# 5V0_12V0_rails.net
KiCad netlist of a schematic drawn in Altium Designer
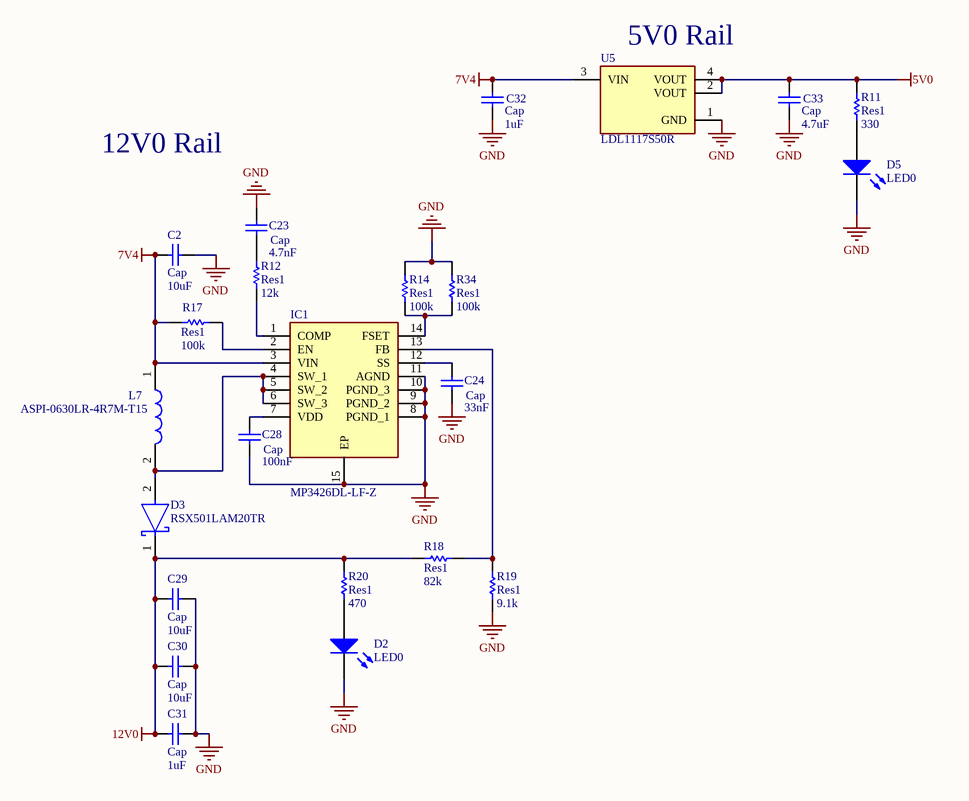
[diagram p0: 5V0 +12V0 rails.SchDoc]

(export (version "E")
  (design (tool "Eeschema 10.0.6"))
  (components
    (comp (ref "C2")
      (value "Cap")
      (footprint "6-0805_M")
      (description "Capacitor")
      (fields (field (name "ALTIUM_VALUE") "10uF") (field (name "PUBLISHER") "Altium Limited"))
      (libsource (lib "Miscellaneous Devices") (part "Cap"))
    )
    (comp (ref "C23")
      (value "Cap")
      (footprint "0402-A")
      (description "Capacitor")
      (fields (field (name "ALTIUM_VALUE") "4.7nF") (field (name "PUBLISHER") "Altium Limited"))
      (libsource (lib "Miscellaneous Devices") (part "Cap"))
    )
    (comp (ref "C24")
      (value "Cap")
      (footprint "0402-A")
      (description "Capacitor")
      (fields (field (name "ALTIUM_VALUE") "33nF") (field (name "PUBLISHER") "Altium Limited"))
      (libsource (lib "Miscellaneous Devices") (part "Cap"))
    )
    (comp (ref "C28")
      (value "Cap")
      (footprint "1608[0603]")
      (description "Capacitor")
      (fields (field (name "ALTIUM_VALUE") "100nF") (field (name "PUBLISHER") "Altium Limited"))
      (libsource (lib "Miscellaneous Devices") (part "Cap"))
    )
    (comp (ref "C29")
      (value "Cap")
      (footprint "6-0805_M")
      (description "Capacitor")
      (fields (field (name "ALTIUM_VALUE") "10uF") (field (name "PUBLISHER") "Altium Limited"))
      (libsource (lib "Miscellaneous Devices") (part "Cap"))
    )
    (comp (ref "C30")
      (value "Cap")
      (footprint "6-0805_M")
      (description "Capacitor")
      (fields (field (name "ALTIUM_VALUE") "10uF") (field (name "PUBLISHER") "Altium Limited"))
      (libsource (lib "Miscellaneous Devices") (part "Cap"))
    )
    (comp (ref "C31")
      (value "Cap")
      (footprint "1608[0603]")
      (description "Capacitor")
      (fields (field (name "ALTIUM_VALUE") "1uF") (field (name "PUBLISHER") "Altium Limited"))
      (libsource (lib "Miscellaneous Devices") (part "Cap"))
    )
    (comp (ref "C32")
      (value "Cap")
      (footprint "1608[0603]")
      (description "Capacitor")
      (fields (field (name "ALTIUM_VALUE") "1uF") (field (name "PUBLISHER") "Altium Limited"))
      (libsource (lib "Miscellaneous Devices") (part "Cap"))
    )
    (comp (ref "C33")
      (value "Cap")
      (footprint "1608[0603]")
      (description "Capacitor")
      (fields (field (name "ALTIUM_VALUE") "4.7uF") (field (name "PUBLISHER") "Altium Limited"))
      (libsource (lib "Miscellaneous Devices") (part "Cap"))
    )
    (comp (ref "D2")
      (value "LED0")
      (footprint "1608[0603]")
      (fields (field (name "PUBLISHER") "Altium Limited"))
      (libsource (lib "Miscellaneous Devices") (part "LED0"))
    )
    (comp (ref "D3")
      (value "RSX501LAM20TR")
      (footprint "FP-PMDTM-MFG")
      (description "DIODE SCHOTTKY 20V 5A PMDTM")
      (fields
        (field (name "OCTOPART") "https://octopart.com/rsx501lam20tr-rohm-82270774")
        (field (name "MANUFACTURER") "Rohm")
      )
      (libsource (lib "Altium Content Vault") (part "1d6ec82d83fb6aee721767c19dac4b9"))
    )
    (comp (ref "D5")
      (value "LED0")
      (footprint "1608[0603]")
      (fields (field (name "PUBLISHER") "Altium Limited"))
      (libsource (lib "Miscellaneous Devices") (part "LED0"))
    )
    (comp (ref "IC1")
      (value "MP3426DL-LF-Z")
      (footprint "SamacSys:SON50P300X400X100-15N-D")
      (description "Integrated Circuit")
      (fields (field (name "MOUSER PART NUMBER") "946-MP3426DL-LF-Z"))
      (libsource (lib "*") (part "MP3426DL-LF-Z"))
    )
    (comp (ref "L7")
      (value "ASPI-0630LR-4R7M-T15")
      (footprint "SamacSys:ASPI-0630LR")
      (description "Inductor")
      (fields (field (name "MOUSER PART NUMBER") "815-ASPI0630LR4R7T15"))
      (libsource (lib "*") (part "ASPI-0630LR-4R7M-T15"))
    )
    (comp (ref "R11")
      (value "Res1")
      (footprint "0402-A")
      (description "Resistor")
      (fields (field (name "ALTIUM_VALUE") "330") (field (name "PUBLISHER") "Altium Limited"))
      (libsource (lib "Miscellaneous Devices") (part "Res1"))
    )
    (comp (ref "R12")
      (value "Res1")
      (footprint "0402-A")
      (description "Resistor")
      (fields (field (name "ALTIUM_VALUE") "12k") (field (name "PUBLISHER") "Altium Limited"))
      (libsource (lib "Miscellaneous Devices") (part "Res1"))
    )
    (comp (ref "R14")
      (value "Res1")
      (footprint "0402-A")
      (description "Resistor")
      (fields (field (name "ALTIUM_VALUE") "100k") (field (name "PUBLISHER") "Altium Limited"))
      (libsource (lib "Miscellaneous Devices") (part "Res1"))
    )
    (comp (ref "R17")
      (value "Res1")
      (footprint "0402-A")
      (description "Resistor")
      (fields (field (name "ALTIUM_VALUE") "100k") (field (name "PUBLISHER") "Altium Limited"))
      (libsource (lib "Miscellaneous Devices") (part "Res1"))
    )
    (comp (ref "R18")
      (value "Res1")
      (footprint "0402-A")
      (description "Resistor")
      (fields (field (name "ALTIUM_VALUE") "82k") (field (name "PUBLISHER") "Altium Limited"))
      (libsource (lib "Miscellaneous Devices") (part "Res1"))
    )
    (comp (ref "R19")
      (value "Res1")
      (footprint "0402-A")
      (description "Resistor")
      (fields (field (name "ALTIUM_VALUE") "9.1k") (field (name "PUBLISHER") "Altium Limited"))
      (libsource (lib "Miscellaneous Devices") (part "Res1"))
    )
    (comp (ref "R20")
      (value "Res1")
      (footprint "6-0805_M")
      (description "Resistor")
      (fields (field (name "ALTIUM_VALUE") "470") (field (name "PUBLISHER") "Altium Limited"))
      (libsource (lib "Miscellaneous Devices") (part "Res1"))
    )
    (comp (ref "R34")
      (value "Res1")
      (footprint "0402-A")
      (description "Resistor")
      (fields (field (name "ALTIUM_VALUE") "100k") (field (name "PUBLISHER") "Altium Limited"))
      (libsource (lib "Miscellaneous Devices") (part "Res1"))
    )
    (comp (ref "U5")
      (value "LDL1117S50R")
      (footprint "FP-SOT-223-0046067_14-MFG")
      (description "IC REG LINEAR 5V 1.2A SOT223")
      (fields
        (field (name "OCTOPART") "https://octopart.com/ldl1117s50r-stmicroelectronics-81876164")
        (field (name "MANUFACTURER") "STMicroelectronics")
      )
      (libsource (lib "Altium Content Vault") (part "a368f1d72361ca9956852d636243424"))
    )
  )
  (nets
    (net (code "1") (name "5V0") (class "Default")
      (node (ref "C33") (pin "2") (pinfunction "2_2") (pintype "passive"))
      (node (ref "R11") (pin "2") (pinfunction "2_2") (pintype "passive"))
      (node (ref "U5") (pin "2") (pinfunction "VOUT_2") (pintype "power_in"))
      (node (ref "U5") (pin "4") (pinfunction "VOUT_4") (pintype "power_in"))
    )
    (net (code "2") (name "7V4") (class "Default")
      (node (ref "C2") (pin "2") (pinfunction "2_2") (pintype "passive"))
      (node (ref "C32") (pin "2") (pinfunction "2_2") (pintype "passive"))
      (node (ref "IC1") (pin "3") (pinfunction "VIN_3") (pintype "passive"))
      (node (ref "L7") (pin "1") (pinfunction "1_1") (pintype "passive"))
      (node (ref "R17") (pin "2") (pinfunction "2_2") (pintype "passive"))
      (node (ref "U5") (pin "3") (pinfunction "VIN_3") (pintype "power_in"))
    )
    (net (code "3") (name "12V0") (class "Default")
      (node (ref "C29") (pin "2") (pinfunction "2_2") (pintype "passive"))
      (node (ref "C30") (pin "2") (pinfunction "2_2") (pintype "passive"))
      (node (ref "C31") (pin "2") (pinfunction "2_2") (pintype "passive"))
      (node (ref "D3") (pin "1") (pinfunction "C_1") (pintype "passive"))
      (node (ref "R18") (pin "2") (pinfunction "2_2") (pintype "passive"))
      (node (ref "R20") (pin "2") (pinfunction "2_2") (pintype "passive"))
    )
    (net (code "4") (name "GND") (class "Default")
      (node (ref "C2") (pin "1") (pinfunction "1_1") (pintype "passive"))
      (node (ref "C23") (pin "2") (pinfunction "2_2") (pintype "passive"))
      (node (ref "C24") (pin "1") (pinfunction "1_1") (pintype "passive"))
      (node (ref "C28") (pin "1") (pinfunction "1_1") (pintype "passive"))
      (node (ref "C29") (pin "1") (pinfunction "1_1") (pintype "passive"))
      (node (ref "C30") (pin "1") (pinfunction "1_1") (pintype "passive"))
      (node (ref "C31") (pin "1") (pinfunction "1_1") (pintype "passive"))
      (node (ref "C32") (pin "1") (pinfunction "1_1") (pintype "passive"))
      (node (ref "C33") (pin "1") (pinfunction "1_1") (pintype "passive"))
      (node (ref "D2") (pin "2") (pinfunction "K_2") (pintype "passive"))
      (node (ref "D5") (pin "2") (pinfunction "K_2") (pintype "passive"))
      (node (ref "IC1") (pin "10") (pinfunction "PGND_3_10") (pintype "passive"))
      (node (ref "IC1") (pin "11") (pinfunction "AGND_11") (pintype "passive"))
      (node (ref "IC1") (pin "15") (pinfunction "EP_15") (pintype "passive"))
      (node (ref "IC1") (pin "8") (pinfunction "PGND_1_8") (pintype "passive"))
      (node (ref "IC1") (pin "9") (pinfunction "PGND_2_9") (pintype "passive"))
      (node (ref "R14") (pin "1") (pinfunction "1_1") (pintype "passive"))
      (node (ref "R19") (pin "1") (pinfunction "1_1") (pintype "passive"))
      (node (ref "R34") (pin "1") (pinfunction "1_1") (pintype "passive"))
      (node (ref "U5") (pin "1") (pinfunction "GND_1") (pintype "power_in"))
    )
    (net (code "5") (name "Net-(C23-Pad1)") (class "Default")
      (node (ref "C23") (pin "1") (pinfunction "1_1") (pintype "passive"))
      (node (ref "R12") (pin "1") (pinfunction "1_1") (pintype "passive"))
    )
    (net (code "6") (name "Net-(D2-A)") (class "Default")
      (node (ref "D2") (pin "1") (pinfunction "A_1") (pintype "passive"))
      (node (ref "R20") (pin "1") (pinfunction "1_1") (pintype "passive"))
    )
    (net (code "7") (name "Net-(D3-A)") (class "Default")
      (node (ref "D3") (pin "2") (pinfunction "A_2") (pintype "passive"))
      (node (ref "IC1") (pin "4") (pinfunction "SW_1_4") (pintype "passive"))
      (node (ref "IC1") (pin "5") (pinfunction "SW_2_5") (pintype "passive"))
      (node (ref "IC1") (pin "6") (pinfunction "SW_3_6") (pintype "passive"))
      (node (ref "L7") (pin "2") (pinfunction "2_2") (pintype "passive"))
    )
    (net (code "8") (name "Net-(D5-A)") (class "Default")
      (node (ref "D5") (pin "1") (pinfunction "A_1") (pintype "passive"))
      (node (ref "R11") (pin "1") (pinfunction "1_1") (pintype "passive"))
    )
    (net (code "9") (name "Net-(IC1-COMP)") (class "Default")
      (node (ref "IC1") (pin "1") (pinfunction "COMP_1") (pintype "passive"))
      (node (ref "R12") (pin "2") (pinfunction "2_2") (pintype "passive"))
    )
    (net (code "10") (name "Net-(IC1-EN)") (class "Default")
      (node (ref "IC1") (pin "2") (pinfunction "EN_2") (pintype "passive"))
      (node (ref "R17") (pin "1") (pinfunction "1_1") (pintype "passive"))
    )
    (net (code "11") (name "Net-(IC1-FB)") (class "Default")
      (node (ref "IC1") (pin "13") (pinfunction "FB_13") (pintype "passive"))
      (node (ref "R18") (pin "1") (pinfunction "1_1") (pintype "passive"))
      (node (ref "R19") (pin "2") (pinfunction "2_2") (pintype "passive"))
    )
    (net (code "12") (name "Net-(IC1-FSET)") (class "Default")
      (node (ref "IC1") (pin "14") (pinfunction "FSET_14") (pintype "passive"))
      (node (ref "R14") (pin "2") (pinfunction "2_2") (pintype "passive"))
      (node (ref "R34") (pin "2") (pinfunction "2_2") (pintype "passive"))
    )
    (net (code "13") (name "Net-(IC1-SS)") (class "Default")
      (node (ref "C24") (pin "2") (pinfunction "2_2") (pintype "passive"))
      (node (ref "IC1") (pin "12") (pinfunction "SS_12") (pintype "passive"))
    )
    (net (code "14") (name "Net-(IC1-VDD)") (class "Default")
      (node (ref "C28") (pin "2") (pinfunction "2_2") (pintype "passive"))
      (node (ref "IC1") (pin "7") (pinfunction "VDD_7") (pintype "passive"))
    )
  )
)
